# boomerang.net
KiCad netlist of a schematic drawn in EAGLE
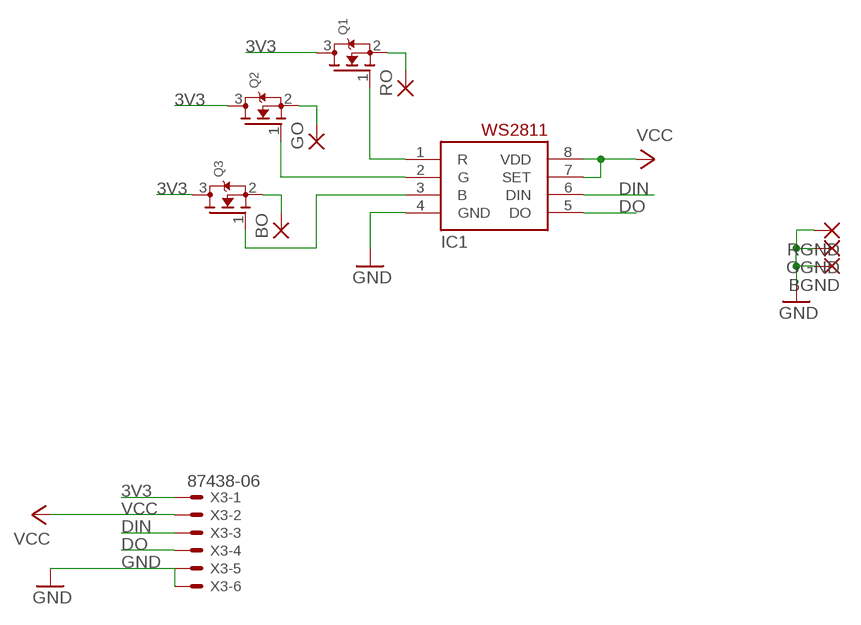
[diagram p0: schematic, sheet 1]

(export (version "E")
  (design (tool "Eeschema 10.0.6"))
  (components
    (comp (ref "BGND")
      (value "SMD2")
      (footprint "eagle-import:SMD1,27-2,54")
      (libsource (lib "eagle-import") (part "SMD2"))
    )
    (comp (ref "BO")
      (value "SMD2")
      (footprint "eagle-import:SMD1,27-2,54")
      (libsource (lib "eagle-import") (part "SMD2"))
    )
    (comp (ref "GGND")
      (value "SMD2")
      (footprint "eagle-import:SMD1,27-2,54")
      (libsource (lib "eagle-import") (part "SMD2"))
    )
    (comp (ref "GO")
      (value "SMD2")
      (footprint "eagle-import:SMD1,27-2,54")
      (libsource (lib "eagle-import") (part "SMD2"))
    )
    (comp (ref "IC1")
      (value "WS2811-SOP8")
      (footprint "eagle-import:SO08-SKINNYPADS")
      (libsource (lib "eagle-import") (part "WS2811-SOP8"))
    )
    (comp (ref "Q1")
      (value "MOSFET-NREFLOW")
      (footprint "eagle-import:SOT23")
      (libsource (lib "eagle-import") (part "MOSFET-NREFLOW"))
    )
    (comp (ref "Q2")
      (value "MOSFET-NREFLOW")
      (footprint "eagle-import:SOT23")
      (libsource (lib "eagle-import") (part "MOSFET-NREFLOW"))
    )
    (comp (ref "Q3")
      (value "MOSFET-NREFLOW")
      (footprint "eagle-import:SOT23")
      (libsource (lib "eagle-import") (part "MOSFET-NREFLOW"))
    )
    (comp (ref "RGND")
      (value "SMD2")
      (footprint "eagle-import:SMD1,27-2,54")
      (libsource (lib "eagle-import") (part "SMD2"))
    )
    (comp (ref "RO")
      (value "SMD2")
      (footprint "eagle-import:SMD1,27-2,54")
      (libsource (lib "eagle-import") (part "SMD2"))
    )
    (comp (ref "X3")
      (value "87438-06")
      (footprint "eagle-import:87438-06")
      (fields (field (name "MPN") "87438-0643"))
      (libsource (lib "eagle-import") (part "87438-06"))
    )
  )
  (nets
    (net (code "1") (name "/3V3") (class "Default")
      (node (ref "Q1") (pin "3") (pinfunction "D_3") (pintype "bidirectional"))
      (node (ref "Q2") (pin "3") (pinfunction "D_3") (pintype "bidirectional"))
      (node (ref "Q3") (pin "3") (pinfunction "D_3") (pintype "bidirectional"))
      (node (ref "X3") (pin "1") (pinfunction "S_1") (pintype "passive"))
    )
    (net (code "2") (name "/DIN") (class "Default")
      (node (ref "IC1") (pin "6") (pinfunction "DIN_6") (pintype "input"))
      (node (ref "X3") (pin "3") (pinfunction "S_3") (pintype "passive"))
    )
    (net (code "3") (name "/DO") (class "Default")
      (node (ref "IC1") (pin "5") (pinfunction "DO_5") (pintype "output"))
      (node (ref "X3") (pin "4") (pinfunction "S_4") (pintype "passive"))
    )
    (net (code "4") (name "GND") (class "Default")
      (node (ref "BGND") (pin "1") (pinfunction "P_1") (pintype "passive"))
      (node (ref "GGND") (pin "1") (pinfunction "P_1") (pintype "passive"))
      (node (ref "IC1") (pin "4") (pinfunction "GND_4") (pintype "power_in"))
      (node (ref "RGND") (pin "1") (pinfunction "P_1") (pintype "passive"))
      (node (ref "X3") (pin "5") (pinfunction "S_5") (pintype "passive"))
      (node (ref "X3") (pin "6") (pinfunction "S_6") (pintype "passive"))
    )
    (net (code "5") (name "Net-(BO-P)") (class "Default")
      (node (ref "BO") (pin "1") (pinfunction "P_1") (pintype "passive"))
      (node (ref "Q3") (pin "2") (pinfunction "S_2") (pintype "bidirectional"))
    )
    (net (code "6") (name "Net-(GO-P)") (class "Default")
      (node (ref "GO") (pin "1") (pinfunction "P_1") (pintype "passive"))
      (node (ref "Q2") (pin "2") (pinfunction "S_2") (pintype "bidirectional"))
    )
    (net (code "7") (name "Net-(IC1-B)") (class "Default")
      (node (ref "IC1") (pin "3") (pinfunction "B_3") (pintype "open_collector"))
      (node (ref "Q3") (pin "1") (pinfunction "G_1") (pintype "bidirectional"))
    )
    (net (code "8") (name "Net-(IC1-G)") (class "Default")
      (node (ref "IC1") (pin "2") (pinfunction "G_2") (pintype "open_collector"))
      (node (ref "Q2") (pin "1") (pinfunction "G_1") (pintype "bidirectional"))
    )
    (net (code "9") (name "Net-(IC1-R)") (class "Default")
      (node (ref "IC1") (pin "1") (pinfunction "R_1") (pintype "open_collector"))
      (node (ref "Q1") (pin "1") (pinfunction "G_1") (pintype "bidirectional"))
    )
    (net (code "10") (name "Net-(Q1-S)") (class "Default")
      (node (ref "Q1") (pin "2") (pinfunction "S_2") (pintype "bidirectional"))
      (node (ref "RO") (pin "1") (pinfunction "P_1") (pintype "passive"))
    )
    (net (code "11") (name "VCC") (class "Default")
      (node (ref "IC1") (pin "7") (pinfunction "SET_7") (pintype "input"))
      (node (ref "IC1") (pin "8") (pinfunction "VDD_8") (pintype "power_in"))
      (node (ref "X3") (pin "2") (pinfunction "S_2") (pintype "passive"))
    )
  )
)
